# Jacdac_Pressure_Sensor.net
KiCad netlist of a schematic drawn in EAGLE
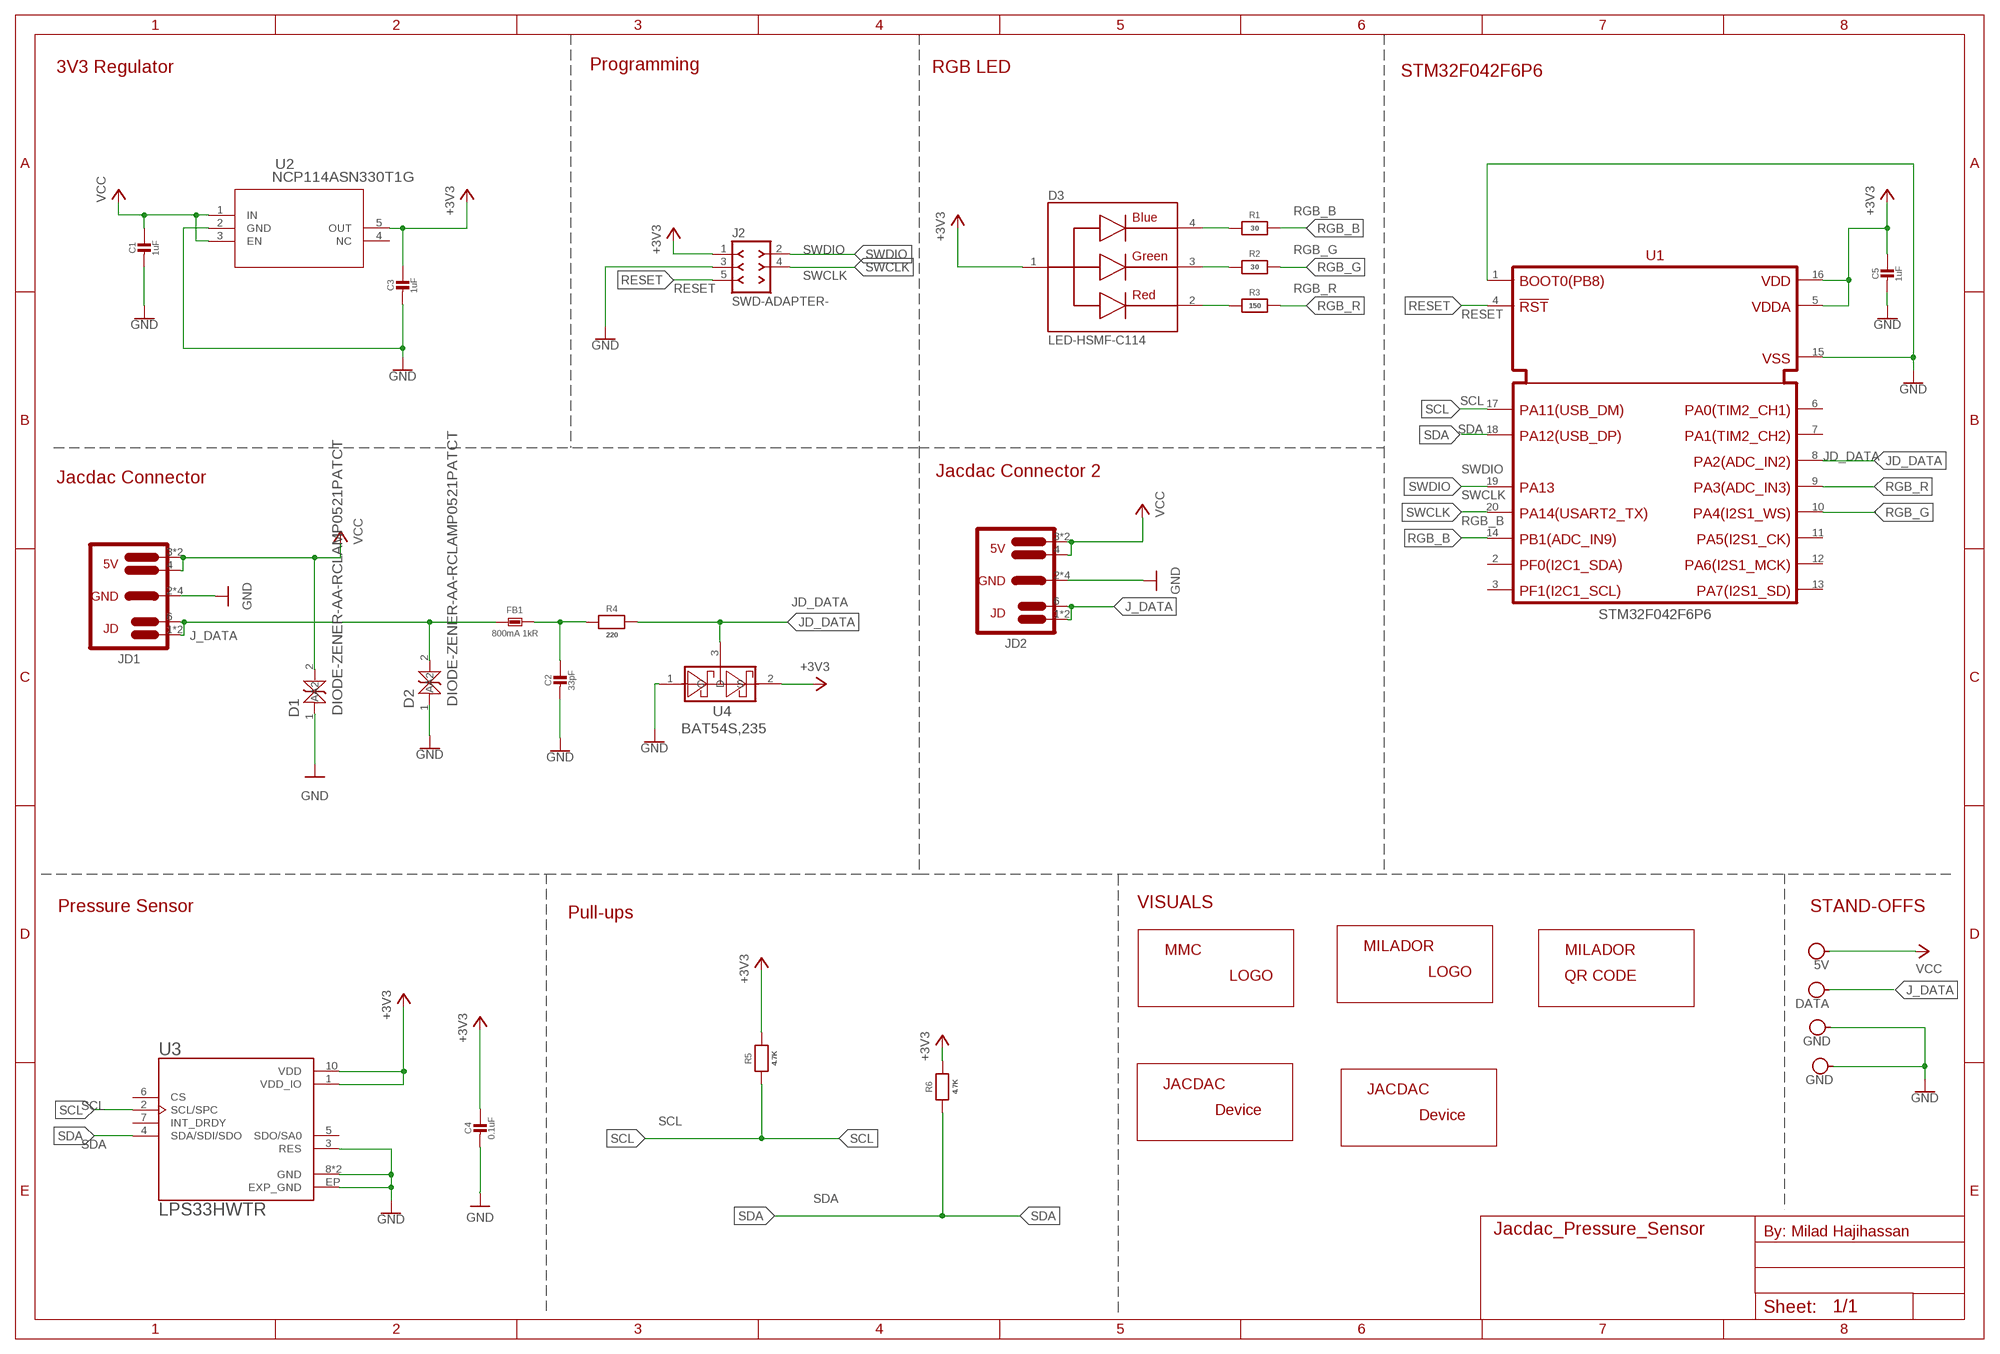
[diagram p0: schematic, sheet 1]

(export (version "E")
  (design (tool "Eeschema 10.0.6"))
  (components
    (comp (ref "C1")
      (value "1uF")
      (footprint "eagle-import:0603-NO")
      (libsource (lib "eagle-import") (part "CAP_CERAMIC-0603-NO"))
    )
    (comp (ref "C2")
      (value "33pF")
      (footprint "eagle-import:0603")
      (libsource (lib "eagle-import") (part "CAP_CERAMIC-0603"))
    )
    (comp (ref "C3")
      (value "1uF")
      (footprint "eagle-import:0603-NO")
      (libsource (lib "eagle-import") (part "CAP_CERAMIC-0603-NO"))
    )
    (comp (ref "C4")
      (value "0.1uF")
      (footprint "eagle-import:0603-NO")
      (libsource (lib "eagle-import") (part "CAP_CERAMIC-0603-NO"))
    )
    (comp (ref "C5")
      (value "1uF")
      (footprint "eagle-import:0603")
      (libsource (lib "eagle-import") (part "CAP_CERAMIC-0603"))
    )
    (comp (ref "D1")
      (value "DIODE-ZENER-AA-RCLAMP0521PATCT")
      (footprint "eagle-import:DIODE-ZENER-0402")
      (fields
        (field (name "MANUFACTURER_PART_NUMBER") "RCLAMP0521PATCT")
        (field (name "COPYRIGHT") "Copyright (C) 2021 Ultra Librarian. All rights reserved.")
      )
      (libsource (lib "eagle-import") (part "DIODE-ZENER-AA-RCLAMP0521PATCT"))
    )
    (comp (ref "D2")
      (value "DIODE-ZENER-AA-RCLAMP0521PATCT")
      (footprint "eagle-import:DIODE-ZENER-0402")
      (fields
        (field (name "MANUFACTURER_PART_NUMBER") "RCLAMP0521PATCT")
        (field (name "COPYRIGHT") "Copyright (C) 2021 Ultra Librarian. All rights reserved.")
      )
      (libsource (lib "eagle-import") (part "DIODE-ZENER-AA-RCLAMP0521PATCT"))
    )
    (comp (ref "D3")
      (value "LED-HSMF-C114")
      (footprint "eagle-import:DIOSC160X150X35-4N")
      (fields (field (name "MF") "Broadcom Limited") (field (name "MP") "HSMF-C114"))
      (libsource (lib "eagle-import") (part "LED-HSMF-C114"))
    )
    (comp (ref "FB1")
      (value "800mA 1kR")
      (footprint "eagle-import:0603-NO")
      (libsource (lib "eagle-import") (part "FERRITE-BEAD-0603-NO"))
    )
    (comp (ref "J2")
      (value "SWD-ADAPTER-")
      (footprint "eagle-import:SWD-ADAPTER")
      (libsource (lib "eagle-import") (part "SWD-ADAPTER-"))
    )
    (comp (ref "J3")
      (value "5V")
      (footprint "eagle-import:M3-HOLE-PWR-OUTL")
      (libsource (lib "eagle-import") (part "JACDAC-M3-PWR-OUTL"))
    )
    (comp (ref "J4")
      (value "DATA")
      (footprint "eagle-import:M3-HOLE-DATA-NOTCH")
      (libsource (lib "eagle-import") (part "JACDAC-M3-DATA-NOTCH"))
    )
    (comp (ref "J5")
      (value "GND")
      (footprint "eagle-import:M3-HOLE-GND")
      (libsource (lib "eagle-import") (part "JACDAC-M3-GND"))
    )
    (comp (ref "J6")
      (value "GND")
      (footprint "eagle-import:M3-HOLE-GND")
      (libsource (lib "eagle-import") (part "JACDAC-M3-GND"))
    )
    (comp (ref "JD1")
      (value "JACDAC-EDGE-OUTIE")
      (footprint "eagle-import:JD-EDGE-OUTIE")
      (libsource (lib "eagle-import") (part "JACDAC-EDGE-OUTIE"))
    )
    (comp (ref "JD2")
      (value "JACDAC-EDGE-OUTIE")
      (footprint "eagle-import:JD-EDGE-OUTIE")
      (libsource (lib "eagle-import") (part "JACDAC-EDGE-OUTIE"))
    )
    (comp (ref "LABEL_JACDAC_PS")
      (value "MILADOR-JACDAC-DEVICE-PS")
      (footprint "eagle-import:JACDAC-PRESSURE-SENSOR")
      (libsource (lib "eagle-import") (part "MILADOR-JACDAC-DEVICE-PS"))
    )
    (comp (ref "LABEL_LPS33HW")
      (value "MILADOR-JACDAC-DEVICE-LPS33HW")
      (footprint "eagle-import:JACDAC-LPS33HW")
      (libsource (lib "eagle-import") (part "MILADOR-JACDAC-DEVICE-LPS33HW"))
    )
    (comp (ref "LABEL_MILADOR")
      (value "MILADOR-LOGO-")
      (footprint "eagle-import:MILADOR_LOGO1")
      (libsource (lib "eagle-import") (part "MILADOR-LOGO-"))
    )
    (comp (ref "LABEL_QR_CODE")
      (value "MILADOR-QR-CODE-JACDAC-GITHUB-PS")
      (footprint "eagle-import:MILADOR_QR_JACDAC_PS")
      (libsource (lib "eagle-import") (part "MILADOR-QR-CODE-JACDAC-GITHUB-PS"))
    )
    (comp (ref "MMC_LOGO")
      (value "MMC_LOGO-XSM")
      (footprint "eagle-import:MMC_X-SMALL_LOGO")
      (libsource (lib "eagle-import") (part "MMC_LOGO-XSM"))
    )
    (comp (ref "R1")
      (value "30")
      (footprint "eagle-import:0603")
      (libsource (lib "eagle-import") (part "RESISTOR-0603"))
    )
    (comp (ref "R2")
      (value "30")
      (footprint "eagle-import:0603")
      (libsource (lib "eagle-import") (part "RESISTOR-0603"))
    )
    (comp (ref "R3")
      (value "150")
      (footprint "eagle-import:0603")
      (libsource (lib "eagle-import") (part "RESISTOR-0603"))
    )
    (comp (ref "R4")
      (value "220")
      (footprint "eagle-import:0603")
      (libsource (lib "eagle-import") (part "RESISTOR-0603"))
    )
    (comp (ref "R5")
      (value "4.7K")
      (footprint "eagle-import:0603")
      (libsource (lib "eagle-import") (part "RESISTOR-0603"))
    )
    (comp (ref "R6")
      (value "4.7K")
      (footprint "eagle-import:0603")
      (libsource (lib "eagle-import") (part "RESISTOR-0603"))
    )
    (comp (ref "U1")
      (value "STM32F042F6P6")
      (footprint "eagle-import:TSSOP20")
      (libsource (lib "eagle-import") (part "STM32F042F6P6"))
    )
    (comp (ref "U2")
      (value "NCP114ASN330T1G")
      (footprint "eagle-import:TSOP-5_ONS")
      (fields (field (name "COPYRIGHT") "Copyright (C) 2021 Ultra Librarian. All rights reserved."))
      (libsource (lib "eagle-import") (part "NCP114ASN330T1G"))
    )
    (comp (ref "U3")
      (value "LPS33HWTR")
      (footprint "eagle-import:PQFN60P330X330X290-11N")
      (fields (field (name "DIGI-KEY_PART_NUMBER") "497-17590-1-ND") (field (name "MF") "STMicroelectronics"))
      (libsource (lib "eagle-import") (part "LPS33HWTR"))
    )
    (comp (ref "U4")
      (value "BAT54S,235")
      (footprint "eagle-import:SOT23-3")
      (fields (field (name "MF") "Diodes") (field (name "MP") "BSS138-7-F"))
      (libsource (lib "eagle-import") (part "BAT54S,235"))
    )
  )
  (nets
    (net (code "1") (name "+3V3") (class "Default")
      (node (ref "C3") (pin "1") (pinfunction "1_1") (pintype "passive"))
      (node (ref "C4") (pin "1") (pinfunction "1_1") (pintype "passive"))
      (node (ref "C5") (pin "1") (pinfunction "1_1") (pintype "passive"))
      (node (ref "D3") (pin "1") (pinfunction "1_1") (pintype "passive"))
      (node (ref "J2") (pin "1") (pinfunction "VCC_1_1") (pintype "passive"))
      (node (ref "R5") (pin "2") (pinfunction "2_2") (pintype "passive"))
      (node (ref "R6") (pin "2") (pinfunction "2_2") (pintype "passive"))
      (node (ref "U1") (pin "16") (pinfunction "VDD_16") (pintype "input"))
      (node (ref "U1") (pin "5") (pinfunction "VDDA_5") (pintype "input"))
      (node (ref "U2") (pin "5") (pinfunction "OUT_5") (pintype "power_in"))
      (node (ref "U3") (pin "1") (pinfunction "VDD_IO_1") (pintype "power_in"))
      (node (ref "U3") (pin "10") (pinfunction "VDD_10") (pintype "power_in"))
      (node (ref "U4") (pin "2") (pinfunction "S_2") (pintype "passive"))
    )
    (net (code "2") (name "GND") (class "Default")
      (node (ref "C1") (pin "2") (pinfunction "2_2") (pintype "passive"))
      (node (ref "C2") (pin "2") (pinfunction "2_2") (pintype "passive"))
      (node (ref "C3") (pin "2") (pinfunction "2_2") (pintype "passive"))
      (node (ref "C4") (pin "2") (pinfunction "2_2") (pintype "passive"))
      (node (ref "C5") (pin "2") (pinfunction "2_2") (pintype "passive"))
      (node (ref "D1") (pin "1") (pinfunction "A_1") (pintype "passive"))
      (node (ref "D2") (pin "1") (pinfunction "A_1") (pintype "passive"))
      (node (ref "J2") (pin "3") (pinfunction "GND_3_3") (pintype "passive"))
      (node (ref "J5") (pin "H") (pinfunction "P$1_H") (pintype "bidirectional"))
      (node (ref "J6") (pin "H") (pinfunction "P$1_H") (pintype "bidirectional"))
      (node (ref "JD1") (pin "2") (pinfunction "1_2") (pintype "power_in"))
      (node (ref "JD1") (pin "5") (pinfunction "1_5") (pintype "power_in"))
      (node (ref "JD1") (pin "P$2") (pinfunction "1_P$2") (pintype "power_in"))
      (node (ref "JD1") (pin "P$4") (pinfunction "1_P$4") (pintype "power_in"))
      (node (ref "JD2") (pin "2") (pinfunction "1_2") (pintype "power_in"))
      (node (ref "JD2") (pin "5") (pinfunction "1_5") (pintype "power_in"))
      (node (ref "JD2") (pin "P$2") (pinfunction "1_P$2") (pintype "power_in"))
      (node (ref "JD2") (pin "P$4") (pinfunction "1_P$4") (pintype "power_in"))
      (node (ref "U1") (pin "1") (pinfunction "BOOT0_1") (pintype "input"))
      (node (ref "U1") (pin "15") (pinfunction "VSS_15") (pintype "input"))
      (node (ref "U2") (pin "2") (pinfunction "GND_2") (pintype "passive"))
      (node (ref "U3") (pin "3") (pinfunction "RES_3") (pintype "passive"))
      (node (ref "U3") (pin "8") (pinfunction "GND_8") (pintype "power_in"))
      (node (ref "U3") (pin "9") (pinfunction "GND_9") (pintype "power_in"))
      (node (ref "U3") (pin "EP") (pinfunction "EXP_GND_EP") (pintype "power_in"))
      (node (ref "U4") (pin "1") (pinfunction "G_1") (pintype "passive"))
    )
    (net (code "3") (name "JD_DATA") (class "Default")
      (node (ref "R4") (pin "2") (pinfunction "2_2") (pintype "passive"))
      (node (ref "U1") (pin "8") (pinfunction "PA2_8") (pintype "bidirectional"))
      (node (ref "U4") (pin "3") (pinfunction "D_3") (pintype "passive"))
    )
    (net (code "4") (name "J_DATA") (class "Default")
      (node (ref "D2") (pin "2") (pinfunction "A2_2") (pintype "passive"))
      (node (ref "FB1") (pin "2") (pinfunction "2_2") (pintype "passive"))
      (node (ref "J4") (pin "H") (pinfunction "P$1_H") (pintype "bidirectional"))
      (node (ref "JD1") (pin "1") (pinfunction "2_1") (pintype "bidirectional"))
      (node (ref "JD1") (pin "6") (pinfunction "6_6") (pintype "bidirectional"))
      (node (ref "JD1") (pin "P$3") (pinfunction "2_P$3") (pintype "bidirectional"))
      (node (ref "JD2") (pin "1") (pinfunction "2_1") (pintype "bidirectional"))
      (node (ref "JD2") (pin "6") (pinfunction "6_6") (pintype "bidirectional"))
      (node (ref "JD2") (pin "P$3") (pinfunction "2_P$3") (pintype "bidirectional"))
    )
    (net (code "5") (name "Net-(C2-Pad1)") (class "Default")
      (node (ref "C2") (pin "1") (pinfunction "1_1") (pintype "passive"))
      (node (ref "FB1") (pin "1") (pinfunction "1_1") (pintype "passive"))
      (node (ref "R4") (pin "1") (pinfunction "1_1") (pintype "passive"))
    )
    (net (code "6") (name "Net-(D3-Pad2)") (class "Default")
      (node (ref "D3") (pin "2") (pinfunction "2_2") (pintype "passive"))
      (node (ref "R3") (pin "1") (pinfunction "1_1") (pintype "passive"))
    )
    (net (code "7") (name "Net-(D3-Pad3)") (class "Default")
      (node (ref "D3") (pin "3") (pinfunction "3_3") (pintype "passive"))
      (node (ref "R2") (pin "1") (pinfunction "1_1") (pintype "passive"))
    )
    (net (code "8") (name "Net-(D3-Pad4)") (class "Default")
      (node (ref "D3") (pin "4") (pinfunction "4_4") (pintype "passive"))
      (node (ref "R1") (pin "1") (pinfunction "1_1") (pintype "passive"))
    )
    (net (code "9") (name "RESET") (class "Default")
      (node (ref "J2") (pin "5") (pinfunction "RESET_5_5") (pintype "passive"))
      (node (ref "U1") (pin "4") (pinfunction "~{RST}_4") (pintype "input"))
    )
    (net (code "10") (name "RGB_B") (class "Default")
      (node (ref "R1") (pin "2") (pinfunction "2_2") (pintype "passive"))
      (node (ref "U1") (pin "14") (pinfunction "PB1_14") (pintype "bidirectional"))
    )
    (net (code "11") (name "RGB_G") (class "Default")
      (node (ref "R2") (pin "2") (pinfunction "2_2") (pintype "passive"))
      (node (ref "U1") (pin "10") (pinfunction "PA4_10") (pintype "bidirectional"))
    )
    (net (code "12") (name "RGB_R") (class "Default")
      (node (ref "R3") (pin "2") (pinfunction "2_2") (pintype "passive"))
      (node (ref "U1") (pin "9") (pinfunction "PA3_9") (pintype "bidirectional"))
    )
    (net (code "13") (name "SCL") (class "Default")
      (node (ref "R5") (pin "1") (pinfunction "1_1") (pintype "passive"))
      (node (ref "U1") (pin "17") (pinfunction "PA11_17") (pintype "bidirectional"))
      (node (ref "U3") (pin "2") (pinfunction "SCL/SPC_2") (pintype "input"))
    )
    (net (code "14") (name "SDA") (class "Default")
      (node (ref "R6") (pin "1") (pinfunction "1_1") (pintype "passive"))
      (node (ref "U1") (pin "18") (pinfunction "PA12_18") (pintype "bidirectional"))
      (node (ref "U3") (pin "4") (pinfunction "SDA/SDI/SDO_4") (pintype "bidirectional"))
    )
    (net (code "15") (name "SWCLK") (class "Default")
      (node (ref "J2") (pin "4") (pinfunction "SWCLK_4_4") (pintype "passive"))
      (node (ref "U1") (pin "20") (pinfunction "PA14_20") (pintype "bidirectional"))
    )
    (net (code "16") (name "SWDIO") (class "Default")
      (node (ref "J2") (pin "2") (pinfunction "SWDIO_2_2") (pintype "passive"))
      (node (ref "U1") (pin "19") (pinfunction "PA13_19") (pintype "bidirectional"))
    )
    (net (code "17") (name "VCC") (class "Default")
      (node (ref "C1") (pin "1") (pinfunction "1_1") (pintype "passive"))
      (node (ref "D1") (pin "2") (pinfunction "A2_2") (pintype "passive"))
      (node (ref "J3") (pin "H") (pinfunction "P$1_H") (pintype "bidirectional"))
      (node (ref "JD1") (pin "3") (pinfunction "3_3") (pintype "power_in"))
      (node (ref "JD1") (pin "4") (pinfunction "4_4") (pintype "power_in"))
      (node (ref "JD1") (pin "P$1") (pinfunction "3_P$1") (pintype "power_in"))
      (node (ref "JD2") (pin "3") (pinfunction "3_3") (pintype "power_in"))
      (node (ref "JD2") (pin "4") (pinfunction "4_4") (pintype "power_in"))
      (node (ref "JD2") (pin "P$1") (pinfunction "3_P$1") (pintype "power_in"))
      (node (ref "U2") (pin "1") (pinfunction "IN_1") (pintype "input"))
      (node (ref "U2") (pin "3") (pinfunction "EN_3") (pintype "passive"))
    )
    (net (code "18") (name "unconnected-(U1-PA0-Pad6)") (class "Default")
      (node (ref "U1") (pin "6") (pinfunction "PA0_6") (pintype "bidirectional"))
    )
    (net (code "19") (name "unconnected-(U1-PA1-Pad7)") (class "Default")
      (node (ref "U1") (pin "7") (pinfunction "PA1_7") (pintype "bidirectional"))
    )
    (net (code "20") (name "unconnected-(U1-PA5-Pad11)") (class "Default")
      (node (ref "U1") (pin "11") (pinfunction "PA5_11") (pintype "bidirectional"))
    )
    (net (code "21") (name "unconnected-(U1-PA6-Pad12)") (class "Default")
      (node (ref "U1") (pin "12") (pinfunction "PA6_12") (pintype "bidirectional"))
    )
    (net (code "22") (name "unconnected-(U1-PA7-Pad13)") (class "Default")
      (node (ref "U1") (pin "13") (pinfunction "PA7_13") (pintype "bidirectional"))
    )
    (net (code "23") (name "unconnected-(U1-PF0-Pad2)") (class "Default")
      (node (ref "U1") (pin "2") (pinfunction "PF0_2") (pintype "bidirectional"))
    )
    (net (code "24") (name "unconnected-(U1-PF1-Pad3)") (class "Default")
      (node (ref "U1") (pin "3") (pinfunction "PF1_3") (pintype "bidirectional"))
    )
    (net (code "25") (name "unconnected-(U2-NC-Pad4)") (class "Default")
      (node (ref "U2") (pin "4") (pinfunction "NC_4") (pintype "no_connect"))
    )
    (net (code "26") (name "unconnected-(U3-CS-Pad6)") (class "Default")
      (node (ref "U3") (pin "6") (pinfunction "CS_6") (pintype "bidirectional"))
    )
    (net (code "27") (name "unconnected-(U3-INT_DRDY-Pad7)") (class "Default")
      (node (ref "U3") (pin "7") (pinfunction "INT_DRDY_7") (pintype "bidirectional"))
    )
    (net (code "28") (name "unconnected-(U3-SDO{slash}SA0-Pad5)") (class "Default")
      (node (ref "U3") (pin "5") (pinfunction "SDO/SA0_5") (pintype "output"))
    )
  )
)
